# Sheet1_1.net
KiCad netlist of a schematic drawn in Altium Designer
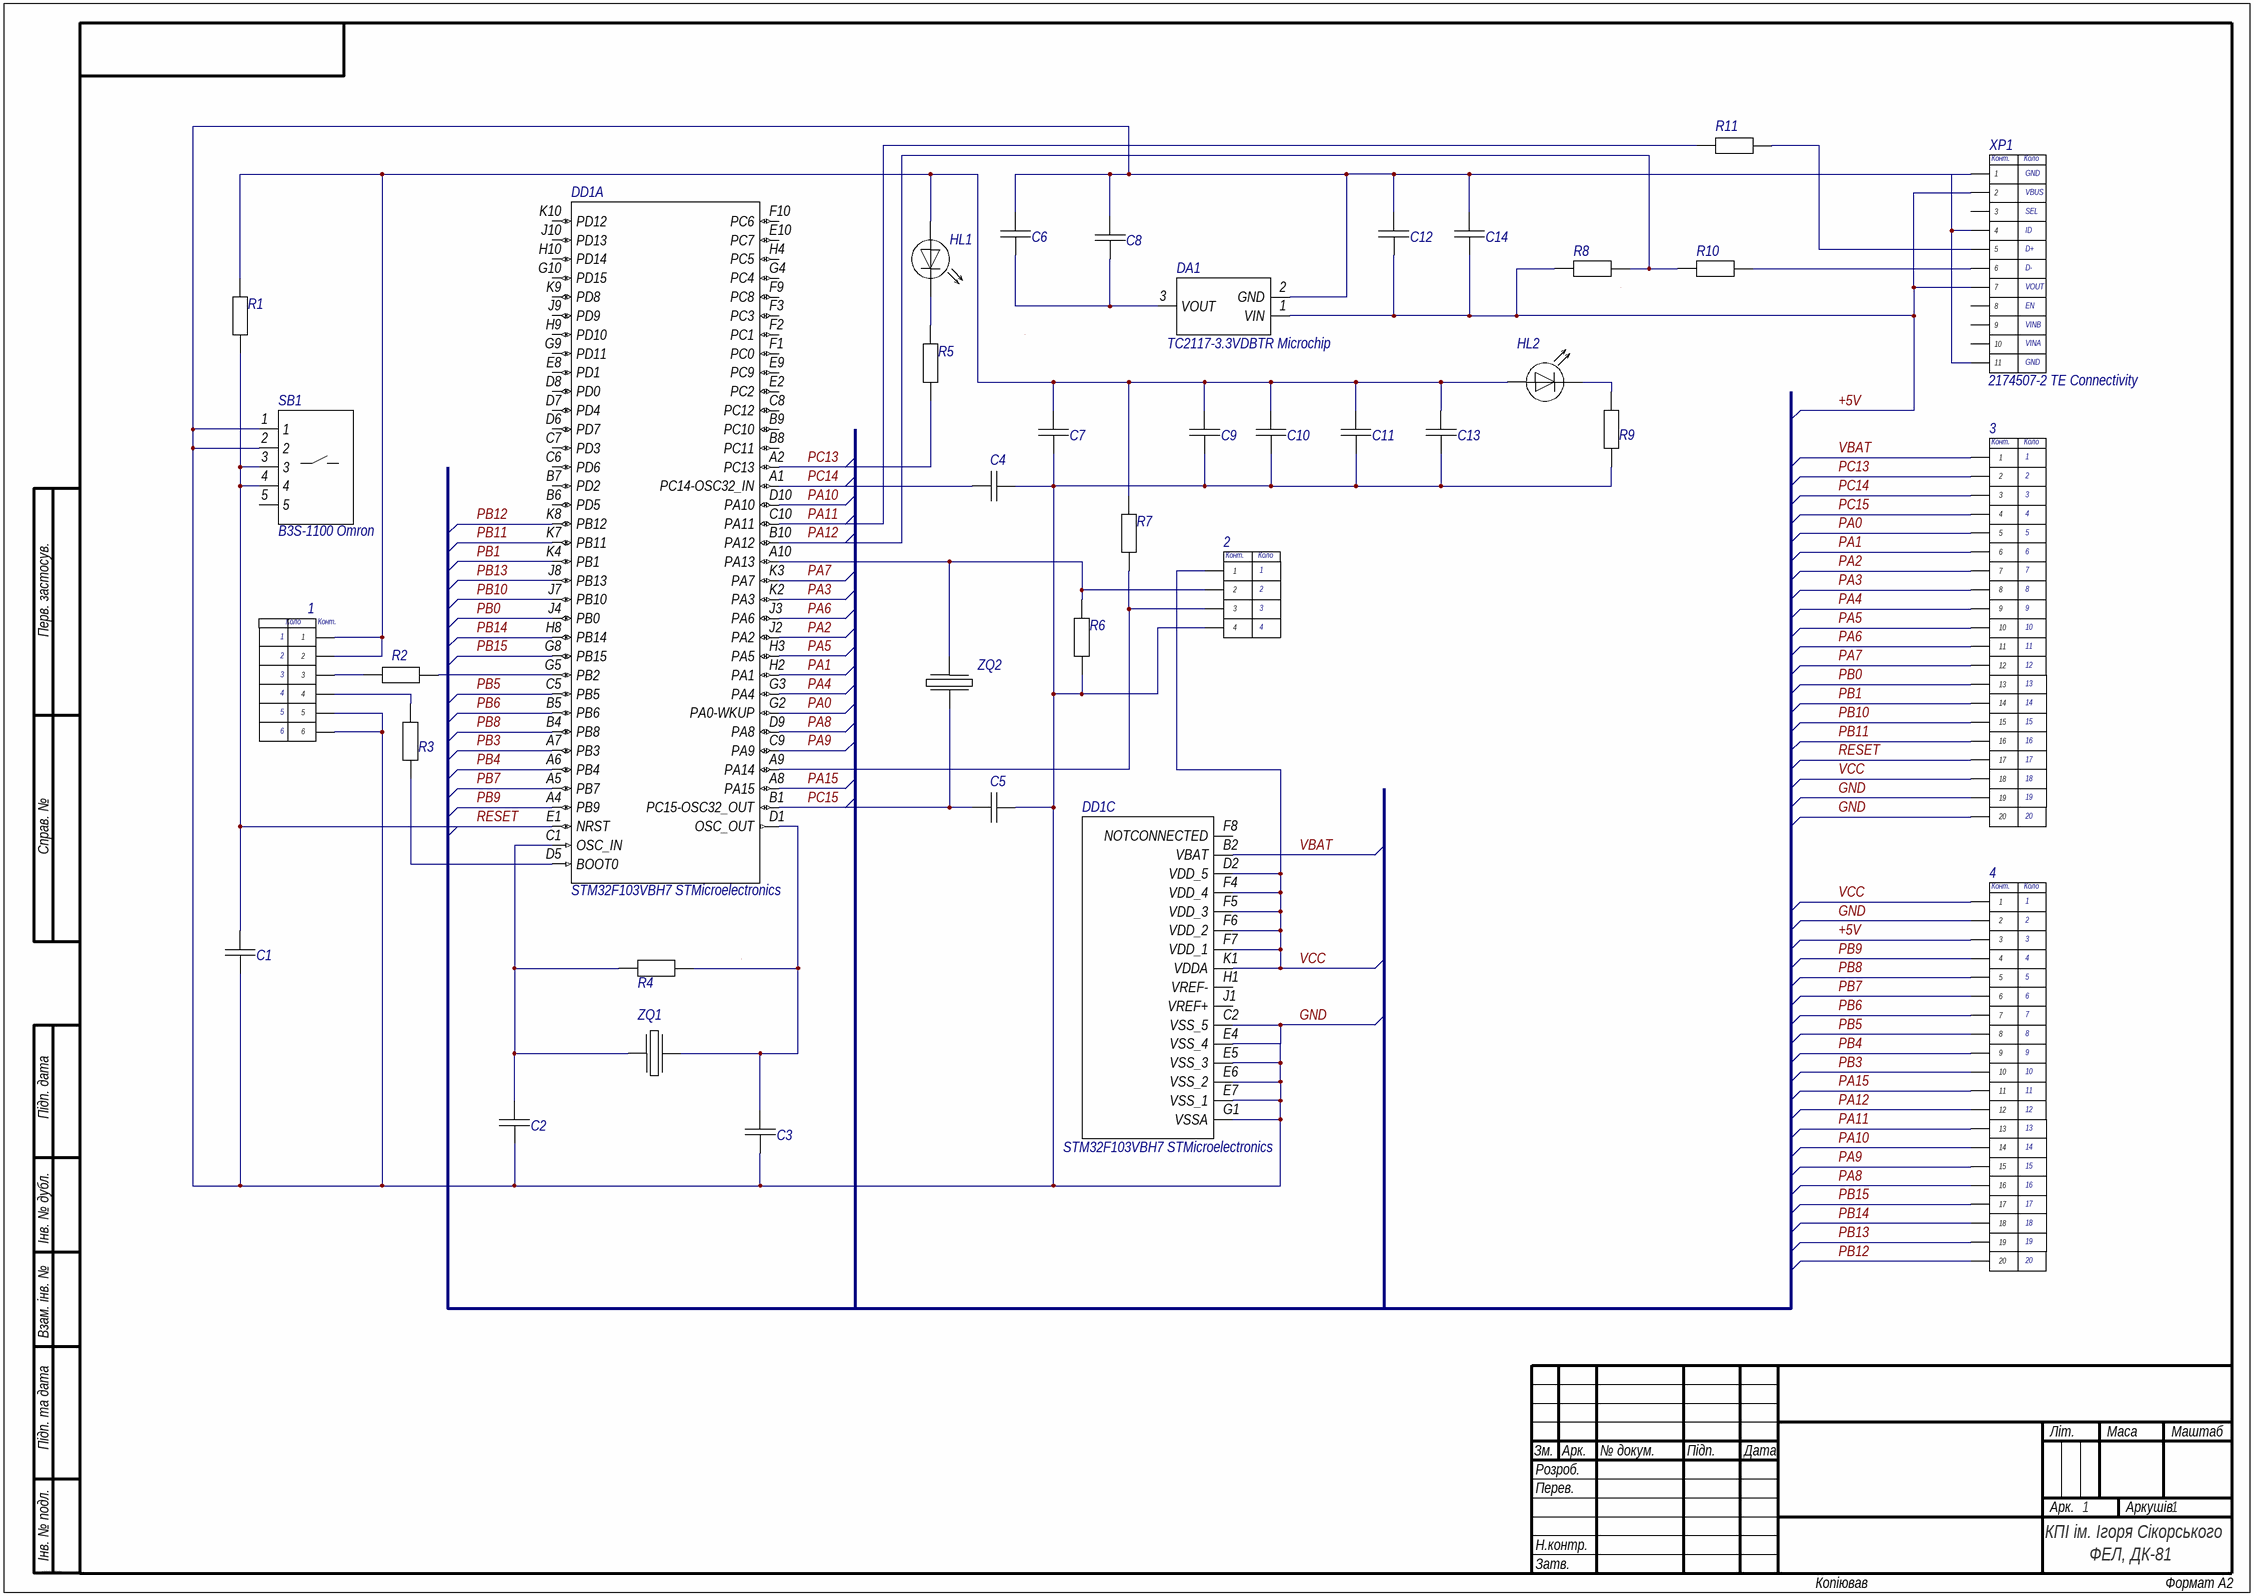
[diagram p0: Sheet1 (1).SchDoc]

(export (version "E")
  (design (tool "Eeschema 10.0.6"))
  (components
    (comp (ref "1")
      (value "pin_boot")
      (footprint "PIN_BOOT")
      (description "pads")
      (libsource (lib "Schlib1") (part "pin_boot"))
    )
    (comp (ref "2")
      (value "pins_jtag")
      (footprint "PIN_JTAG")
      (description "pads")
      (libsource (lib "Schlib1") (part "pins_jtag"))
    )
    (comp (ref "3")
      (value "pin_left")
      (footprint "pin_left")
      (description "pads")
      (libsource (lib "Schlib1") (part "pin_left"))
    )
    (comp (ref "4")
      (value "pin_right")
      (footprint "pin_right")
      (description "pads")
      (libsource (lib "Schlib1") (part "pin_right"))
    )
    (comp (ref "C1")
      (value "0603 63 В 1 мкФ 10% *")
      (footprint "C_0603")
      (fields (field (name "VOLTAGE") "63 В") (field (name "TOLERANCE") "10%"))
      (libsource (lib "Schlib1") (part "C 1 мкФ"))
    )
    (comp (ref "C2")
      (value "0603 63 В 20 пФ 10% *")
      (footprint "C_0603")
      (fields (field (name "VOLTAGE") "63 В") (field (name "TOLERANCE") "10%"))
      (libsource (lib "Schlib1") (part "C 20 пФ"))
    )
    (comp (ref "C3")
      (value "0603 63 В 20 пФ 10% *")
      (footprint "C_0603")
      (fields (field (name "VOLTAGE") "63 В") (field (name "TOLERANCE") "10%"))
      (libsource (lib "Schlib1") (part "C 20 пФ"))
    )
    (comp (ref "C4")
      (value "0603 63 В 20 пФ 10% *")
      (footprint "C_0603")
      (fields (field (name "VOLTAGE") "63 В") (field (name "TOLERANCE") "10%"))
      (libsource (lib "Schlib1") (part "C 20 пФ"))
    )
    (comp (ref "C5")
      (value "0603 63 В 20 пФ 10% *")
      (footprint "C_0603")
      (fields (field (name "VOLTAGE") "63 В") (field (name "TOLERANCE") "10%"))
      (libsource (lib "Schlib1") (part "C 20 пФ"))
    )
    (comp (ref "C6")
      (value "0603 63 В 100 нФ 10% *")
      (footprint "C_0603")
      (fields (field (name "VOLTAGE") "63 В") (field (name "TOLERANCE") "10%"))
      (libsource (lib "Schlib1") (part "C 100 нФ"))
    )
    (comp (ref "C7")
      (value "0603 63 В 100 нФ 10% *")
      (footprint "C_0603")
      (fields (field (name "VOLTAGE") "63 В") (field (name "TOLERANCE") "10%"))
      (libsource (lib "Schlib1") (part "C 100 нФ"))
    )
    (comp (ref "C8")
      (value "CASE-C_6032 63 В 330 мкФ 10% *")
      (footprint "CAPMP6.3X3.2_2.8N_KEM")
      (fields (field (name "VOLTAGE") "63 В") (field (name "TOLERANCE") "10%"))
      (libsource (lib "Schlib1") (part "C 330 мкФ"))
    )
    (comp (ref "C9")
      (value "0603 63 В 100 нФ 10% *")
      (footprint "C_0603")
      (fields (field (name "VOLTAGE") "63 В") (field (name "TOLERANCE") "10%"))
      (libsource (lib "Schlib1") (part "C 100 нФ"))
    )
    (comp (ref "C10")
      (value "0603 63 В 100 нФ 10% *")
      (footprint "C_0603")
      (fields (field (name "VOLTAGE") "63 В") (field (name "TOLERANCE") "10%"))
      (libsource (lib "Schlib1") (part "C 100 нФ"))
    )
    (comp (ref "C11")
      (value "0603 63 В 100 нФ 10% *")
      (footprint "C_0603")
      (fields (field (name "VOLTAGE") "63 В") (field (name "TOLERANCE") "10%"))
      (libsource (lib "Schlib1") (part "C 100 нФ"))
    )
    (comp (ref "C12")
      (value "CASE-C_6032 63 В 100 мкФ 10% *")
      (footprint "CAPMP6.3X3.2_2.8N_KEM")
      (fields (field (name "VOLTAGE") "63 В") (field (name "TOLERANCE") "10%"))
      (libsource (lib "Schlib1") (part "C 100 мкФ"))
    )
    (comp (ref "C13")
      (value "0603 63 В 100 нФ 10% *")
      (footprint "C_0603")
      (fields (field (name "VOLTAGE") "63 В") (field (name "TOLERANCE") "10%"))
      (libsource (lib "Schlib1") (part "C 100 нФ"))
    )
    (comp (ref "C14")
      (value "CASE-C_6032 63 В 100 мкФ 10% *")
      (footprint "CAPMP6.3X3.2_2.8N_KEM")
      (fields (field (name "VOLTAGE") "63 В") (field (name "TOLERANCE") "10%"))
      (libsource (lib "Schlib1") (part "C 100 мкФ"))
    )
    (comp (ref "DA1")
      (value "TC2117-3.3VDBTR Microchip")
      (footprint "TC2117")
      (fields (field (name "MANUFACTURER") "Microchip"))
      (libsource (lib "Schlib1") (part "TC2117-3.3VDBTR"))
    )
    (comp (ref "DD1")
      (value "STM32F103VBH7 STMicroelectronics")
      (footprint "LFBGA100")
      (fields (field (name "MANUFACTURER") "STMicroelectronics"))
      (libsource (lib "Schlib1") (part "STM32F103VBH7"))
    )
    (comp (ref "HL1")
      (value "XL-0603QYGC KENTO")
      (footprint "LED_DIALIGHT_598_DIA-M")
      (fields (field (name "MANUFACTURER") "KENTO"))
      (libsource (lib "Schlib1") (part "LED-0603"))
    )
    (comp (ref "HL2")
      (value "XL-0603QYGC KENTO")
      (footprint "LED_DIALIGHT_598_DIA-M")
      (fields (field (name "MANUFACTURER") "KENTO"))
      (libsource (lib "Schlib1") (part "LED-0603"))
    )
    (comp (ref "R1")
      (value "R-0603 0.1 Вт 10 кОм 10% Yageo")
      (footprint "R_0603")
      (fields
        (field (name "POWER") "0.1 Вт")
        (field (name "TOLERANCE") "10%")
        (field (name "MANUFACTURER") "Yageo")
      )
      (libsource (lib "Schlib1") (part "R 10 кОм"))
    )
    (comp (ref "R2")
      (value "R-0603 0.1 Вт 100 кОм 10% Yageo")
      (footprint "R_0603")
      (fields
        (field (name "POWER") "0.1 Вт")
        (field (name "TOLERANCE") "10%")
        (field (name "MANUFACTURER") "Yageo")
      )
      (libsource (lib "") (part "R 100 кОм_1"))
    )
    (comp (ref "R3")
      (value "R-0603 0.1 Вт 100 кОм 10% Yageo")
      (footprint "R_0603")
      (fields
        (field (name "POWER") "0.1 Вт")
        (field (name "TOLERANCE") "10%")
        (field (name "MANUFACTURER") "Yageo")
      )
      (libsource (lib "Schlib1") (part "R 100 кОм"))
    )
    (comp (ref "R4")
      (value "R-0603 0.1 Вт 1 МОм 10% Yageo")
      (footprint "R_0603")
      (fields
        (field (name "POWER") "0.1 Вт")
        (field (name "TOLERANCE") "10%")
        (field (name "MANUFACTURER") "Yageo")
      )
      (libsource (lib "Schlib1") (part "R 1 МОм"))
    )
    (comp (ref "R5")
      (value "R-0603 0.1 Вт 510 Ом 10% Yageo")
      (footprint "R_0603")
      (fields
        (field (name "POWER") "0.1 Вт")
        (field (name "TOLERANCE") "10%")
        (field (name "MANUFACTURER") "Yageo")
      )
      (libsource (lib "Schlib1") (part "R 510 Ом"))
    )
    (comp (ref "R6")
      (value "R-0603 0.1 Вт 10 кОм 10% Yageo")
      (footprint "R_0603")
      (fields
        (field (name "POWER") "0.1 Вт")
        (field (name "TOLERANCE") "10%")
        (field (name "MANUFACTURER") "Yageo")
      )
      (libsource (lib "Schlib1") (part "R 10 кОм"))
    )
    (comp (ref "R7")
      (value "R-0603 0.1 Вт 10 кОм 10% Yageo")
      (footprint "R_0603")
      (fields
        (field (name "POWER") "0.1 Вт")
        (field (name "TOLERANCE") "10%")
        (field (name "MANUFACTURER") "Yageo")
      )
      (libsource (lib "Schlib1") (part "R 10 кОм"))
    )
    (comp (ref "R8")
      (value "R-0603 0.1 Вт 1.5 кОм 10% Yageo")
      (footprint "R_0603")
      (fields
        (field (name "POWER") "0.1 Вт")
        (field (name "TOLERANCE") "10%")
        (field (name "MANUFACTURER") "Yageo")
      )
      (libsource (lib "Schlib1") (part "R 1.5 кОм"))
    )
    (comp (ref "R9")
      (value "R-0603 0.1 Вт 510 Ом 10% Yageo")
      (footprint "R_0603")
      (fields
        (field (name "POWER") "0.1 Вт")
        (field (name "TOLERANCE") "10%")
        (field (name "MANUFACTURER") "Yageo")
      )
      (libsource (lib "Schlib1") (part "R 510 Ом"))
    )
    (comp (ref "R10")
      (value "R-0603 0.1 Вт 20 Ом 10% Yageo")
      (footprint "R_0603")
      (fields
        (field (name "POWER") "0.1 Вт")
        (field (name "TOLERANCE") "10%")
        (field (name "MANUFACTURER") "Yageo")
      )
      (libsource (lib "Schlib1") (part "R 20 Ом"))
    )
    (comp (ref "R11")
      (value "R-0603 0.1 Вт 20 Ом 10% Yageo")
      (footprint "R_0603")
      (fields
        (field (name "POWER") "0.1 Вт")
        (field (name "TOLERANCE") "10%")
        (field (name "MANUFACTURER") "Yageo")
      )
      (libsource (lib "Schlib1") (part "R 20 Ом"))
    )
    (comp (ref "SB1")
      (value "B3S-1100 Omron")
      (footprint "SW_B3S-1100_OMR")
      (fields (field (name "MANUFACTURER") "Omron"))
      (libsource (lib "Schlib1") (part "B3S-1100"))
    )
    (comp (ref "XP1")
      (value "2174507-2 TE Connectivity")
      (footprint "CONN5_2013499-1_TEC - duplicate")
      (description "usb")
      (fields (field (name "MANUFACTURER") "TE Connectivity"))
      (libsource (lib "Schlib1") (part "2174507-2"))
    )
    (comp (ref "ZQ1")
      (value "OSC_8M LCSC")
      (footprint "HC-49S")
      (fields (field (name "MANUFACTURER") "LCSC"))
      (libsource (lib "Schlib1") (part "OSC_8M"))
    )
    (comp (ref "ZQ2")
      (value "OSC_32.7K LCSC")
      (footprint "SOJ_MC-306_EPS")
      (fields (field (name "MANUFACTURER") "LCSC"))
      (libsource (lib "Schlib1") (part "OSC_32.7K"))
    )
  )
  (nets
    (net (code "1") (name "/+5V") (class "Default")
      (node (ref "4") (pin "3") (pinfunction "3_3") (pintype "passive"))
      (node (ref "C12") (pin "1") (pinfunction "1_1") (pintype "passive"))
      (node (ref "C14") (pin "1") (pinfunction "1_1") (pintype "passive"))
      (node (ref "DA1") (pin "1") (pinfunction "VIN_1") (pintype "passive"))
      (node (ref "R8") (pin "1") (pinfunction "1_1") (pintype "passive"))
      (node (ref "XP1") (pin "2") (pinfunction "2_2") (pintype "passive"))
      (node (ref "XP1") (pin "7") (pinfunction "7_7") (pintype "passive"))
    )
    (net (code "2") (name "/GND") (class "Default")
      (node (ref "1") (pin "5") (pinfunction "5_5") (pintype "passive"))
      (node (ref "1") (pin "6") (pinfunction "6_6") (pintype "passive"))
      (node (ref "2") (pin "4") (pinfunction "4_4") (pintype "passive"))
      (node (ref "3") (pin "19") (pinfunction "19_19") (pintype "passive"))
      (node (ref "3") (pin "20") (pinfunction "20_20") (pintype "passive"))
      (node (ref "4") (pin "2") (pinfunction "2_2") (pintype "passive"))
      (node (ref "C1") (pin "1") (pinfunction "1_1") (pintype "passive"))
      (node (ref "C10") (pin "1") (pinfunction "1_1") (pintype "passive"))
      (node (ref "C11") (pin "1") (pinfunction "1_1") (pintype "passive"))
      (node (ref "C12") (pin "2") (pinfunction "2_2") (pintype "passive"))
      (node (ref "C13") (pin "1") (pinfunction "1_1") (pintype "passive"))
      (node (ref "C14") (pin "2") (pinfunction "2_2") (pintype "passive"))
      (node (ref "C2") (pin "1") (pinfunction "1_1") (pintype "passive"))
      (node (ref "C3") (pin "1") (pinfunction "1_1") (pintype "passive"))
      (node (ref "C4") (pin "2") (pinfunction "2_2") (pintype "passive"))
      (node (ref "C5") (pin "2") (pinfunction "2_2") (pintype "passive"))
      (node (ref "C6") (pin "2") (pinfunction "2_2") (pintype "passive"))
      (node (ref "C7") (pin "1") (pinfunction "1_1") (pintype "passive"))
      (node (ref "C8") (pin "2") (pinfunction "2_2") (pintype "passive"))
      (node (ref "C9") (pin "1") (pinfunction "1_1") (pintype "passive"))
      (node (ref "DA1") (pin "2") (pinfunction "GND_2") (pintype "passive"))
      (node (ref "DD1") (pin "C2") (pinfunction "VSS_5_C2") (pintype "power_in"))
      (node (ref "DD1") (pin "E4") (pinfunction "VSS_4_E4") (pintype "power_in"))
      (node (ref "DD1") (pin "E5") (pinfunction "VSS_3_E5") (pintype "power_in"))
      (node (ref "DD1") (pin "E6") (pinfunction "VSS_2_E6") (pintype "power_in"))
      (node (ref "DD1") (pin "E7") (pinfunction "VSS_1_E7") (pintype "power_in"))
      (node (ref "DD1") (pin "G1") (pinfunction "VSSA_G1") (pintype "power_in"))
      (node (ref "R6") (pin "1") (pinfunction "1_1") (pintype "passive"))
      (node (ref "R9") (pin "1") (pinfunction "1_1") (pintype "passive"))
      (node (ref "SB1") (pin "1") (pinfunction "1_1") (pintype "passive"))
      (node (ref "SB1") (pin "2") (pinfunction "2_2") (pintype "passive"))
      (node (ref "XP1") (pin "1") (pinfunction "1_1") (pintype "passive"))
      (node (ref "XP1") (pin "11") (pinfunction "11_11") (pintype "passive"))
      (node (ref "XP1") (pin "4") (pinfunction "4_4") (pintype "passive"))
    )
    (net (code "3") (name "/PA0") (class "Default")
      (node (ref "3") (pin "5") (pinfunction "5_5") (pintype "passive"))
      (node (ref "DD1") (pin "G2") (pinfunction "PA0-WKUP_G2") (pintype "bidirectional"))
    )
    (net (code "4") (name "/PA1") (class "Default")
      (node (ref "3") (pin "6") (pinfunction "6_6") (pintype "passive"))
      (node (ref "DD1") (pin "H2") (pinfunction "PA1_H2") (pintype "bidirectional"))
    )
    (net (code "5") (name "/PA2") (class "Default")
      (node (ref "3") (pin "7") (pinfunction "7_7") (pintype "passive"))
      (node (ref "DD1") (pin "J2") (pinfunction "PA2_J2") (pintype "bidirectional"))
    )
    (net (code "6") (name "/PA3") (class "Default")
      (node (ref "3") (pin "8") (pinfunction "8_8") (pintype "passive"))
      (node (ref "DD1") (pin "K2") (pinfunction "PA3_K2") (pintype "bidirectional"))
    )
    (net (code "7") (name "/PA4") (class "Default")
      (node (ref "3") (pin "9") (pinfunction "9_9") (pintype "passive"))
      (node (ref "DD1") (pin "G3") (pinfunction "PA4_G3") (pintype "bidirectional"))
    )
    (net (code "8") (name "/PA5") (class "Default")
      (node (ref "3") (pin "10") (pinfunction "10_10") (pintype "passive"))
      (node (ref "DD1") (pin "H3") (pinfunction "PA5_H3") (pintype "bidirectional"))
    )
    (net (code "9") (name "/PA6") (class "Default")
      (node (ref "3") (pin "11") (pinfunction "11_11") (pintype "passive"))
      (node (ref "DD1") (pin "J3") (pinfunction "PA6_J3") (pintype "bidirectional"))
    )
    (net (code "10") (name "/PA7") (class "Default")
      (node (ref "3") (pin "12") (pinfunction "12_12") (pintype "passive"))
      (node (ref "DD1") (pin "K3") (pinfunction "PA7_K3") (pintype "bidirectional"))
    )
    (net (code "11") (name "/PA8") (class "Default")
      (node (ref "4") (pin "16") (pinfunction "16_16") (pintype "passive"))
      (node (ref "DD1") (pin "D9") (pinfunction "PA8_D9") (pintype "bidirectional"))
    )
    (net (code "12") (name "/PA9") (class "Default")
      (node (ref "4") (pin "15") (pinfunction "15_15") (pintype "passive"))
      (node (ref "DD1") (pin "C9") (pinfunction "PA9_C9") (pintype "bidirectional"))
    )
    (net (code "13") (name "/PA10") (class "Default")
      (node (ref "4") (pin "14") (pinfunction "14_14") (pintype "passive"))
      (node (ref "DD1") (pin "D10") (pinfunction "PA10_D10") (pintype "bidirectional"))
    )
    (net (code "14") (name "/PA11") (class "Default")
      (node (ref "4") (pin "13") (pinfunction "13_13") (pintype "passive"))
      (node (ref "DD1") (pin "C10") (pinfunction "PA11_C10") (pintype "bidirectional"))
      (node (ref "R11") (pin "1") (pinfunction "1_1") (pintype "passive"))
    )
    (net (code "15") (name "/PA12") (class "Default")
      (node (ref "4") (pin "12") (pinfunction "12_12") (pintype "passive"))
      (node (ref "DD1") (pin "B10") (pinfunction "PA12_B10") (pintype "bidirectional"))
      (node (ref "R10") (pin "1") (pinfunction "1_1") (pintype "passive"))
      (node (ref "R8") (pin "2") (pinfunction "2_2") (pintype "passive"))
    )
    (net (code "16") (name "/PA15") (class "Default")
      (node (ref "4") (pin "11") (pinfunction "11_11") (pintype "passive"))
      (node (ref "DD1") (pin "A8") (pinfunction "PA15_A8") (pintype "bidirectional"))
    )
    (net (code "17") (name "/PB0") (class "Default")
      (node (ref "3") (pin "13") (pinfunction "13_13") (pintype "passive"))
      (node (ref "DD1") (pin "J4") (pinfunction "PB0_J4") (pintype "bidirectional"))
    )
    (net (code "18") (name "/PB1") (class "Default")
      (node (ref "3") (pin "14") (pinfunction "14_14") (pintype "passive"))
      (node (ref "DD1") (pin "K4") (pinfunction "PB1_K4") (pintype "bidirectional"))
    )
    (net (code "19") (name "/PB3") (class "Default")
      (node (ref "4") (pin "10") (pinfunction "10_10") (pintype "passive"))
      (node (ref "DD1") (pin "A7") (pinfunction "PB3_A7") (pintype "bidirectional"))
    )
    (net (code "20") (name "/PB4") (class "Default")
      (node (ref "4") (pin "9") (pinfunction "9_9") (pintype "passive"))
      (node (ref "DD1") (pin "A6") (pinfunction "PB4_A6") (pintype "bidirectional"))
    )
    (net (code "21") (name "/PB5") (class "Default")
      (node (ref "4") (pin "8") (pinfunction "8_8") (pintype "passive"))
      (node (ref "DD1") (pin "C5") (pinfunction "PB5_C5") (pintype "bidirectional"))
    )
    (net (code "22") (name "/PB6") (class "Default")
      (node (ref "4") (pin "7") (pinfunction "7_7") (pintype "passive"))
      (node (ref "DD1") (pin "B5") (pinfunction "PB6_B5") (pintype "bidirectional"))
    )
    (net (code "23") (name "/PB7") (class "Default")
      (node (ref "4") (pin "6") (pinfunction "6_6") (pintype "passive"))
      (node (ref "DD1") (pin "A5") (pinfunction "PB7_A5") (pintype "bidirectional"))
    )
    (net (code "24") (name "/PB8") (class "Default")
      (node (ref "4") (pin "5") (pinfunction "5_5") (pintype "passive"))
      (node (ref "DD1") (pin "B4") (pinfunction "PB8_B4") (pintype "bidirectional"))
    )
    (net (code "25") (name "/PB9") (class "Default")
      (node (ref "4") (pin "4") (pinfunction "4_4") (pintype "passive"))
      (node (ref "DD1") (pin "A4") (pinfunction "PB9_A4") (pintype "bidirectional"))
    )
    (net (code "26") (name "/PB10") (class "Default")
      (node (ref "3") (pin "15") (pinfunction "15_15") (pintype "passive"))
      (node (ref "DD1") (pin "J7") (pinfunction "PB10_J7") (pintype "bidirectional"))
    )
    (net (code "27") (name "/PB11") (class "Default")
      (node (ref "3") (pin "16") (pinfunction "16_16") (pintype "passive"))
      (node (ref "DD1") (pin "K7") (pinfunction "PB11_K7") (pintype "bidirectional"))
    )
    (net (code "28") (name "/PB12") (class "Default")
      (node (ref "4") (pin "20") (pinfunction "20_20") (pintype "passive"))
      (node (ref "DD1") (pin "K8") (pinfunction "PB12_K8") (pintype "bidirectional"))
    )
    (net (code "29") (name "/PB13") (class "Default")
      (node (ref "4") (pin "19") (pinfunction "19_19") (pintype "passive"))
      (node (ref "DD1") (pin "J8") (pinfunction "PB13_J8") (pintype "bidirectional"))
    )
    (net (code "30") (name "/PB14") (class "Default")
      (node (ref "4") (pin "18") (pinfunction "18_18") (pintype "passive"))
      (node (ref "DD1") (pin "H8") (pinfunction "PB14_H8") (pintype "bidirectional"))
    )
    (net (code "31") (name "/PB15") (class "Default")
      (node (ref "4") (pin "17") (pinfunction "17_17") (pintype "passive"))
      (node (ref "DD1") (pin "G8") (pinfunction "PB15_G8") (pintype "bidirectional"))
    )
    (net (code "32") (name "/PC13") (class "Default")
      (node (ref "3") (pin "2") (pinfunction "2_2") (pintype "passive"))
      (node (ref "DD1") (pin "A2") (pinfunction "PC13_A2") (pintype "bidirectional"))
      (node (ref "R5") (pin "1") (pinfunction "1_1") (pintype "passive"))
    )
    (net (code "33") (name "/PC14") (class "Default")
      (node (ref "3") (pin "3") (pinfunction "3_3") (pintype "passive"))
      (node (ref "C4") (pin "1") (pinfunction "1_1") (pintype "passive"))
      (node (ref "DD1") (pin "A1") (pinfunction "PC14-OSC32_IN_A1") (pintype "bidirectional"))
    )
    (net (code "34") (name "/PC15") (class "Default")
      (node (ref "3") (pin "4") (pinfunction "4_4") (pintype "passive"))
      (node (ref "C5") (pin "1") (pinfunction "1_1") (pintype "passive"))
      (node (ref "DD1") (pin "B1") (pinfunction "PC15-OSC32_OUT_B1") (pintype "bidirectional"))
      (node (ref "ZQ2") (pin "2") (pinfunction "2_2") (pintype "passive"))
    )
    (net (code "35") (name "/RESET") (class "Default")
      (node (ref "3") (pin "17") (pinfunction "17_17") (pintype "passive"))
      (node (ref "C1") (pin "2") (pinfunction "2_2") (pintype "passive"))
      (node (ref "DD1") (pin "E1") (pinfunction "NRST_E1") (pintype "bidirectional"))
      (node (ref "R1") (pin "1") (pinfunction "1_1") (pintype "passive"))
      (node (ref "SB1") (pin "3") (pinfunction "3_3") (pintype "passive"))
      (node (ref "SB1") (pin "4") (pinfunction "4_4") (pintype "passive"))
    )
    (net (code "36") (name "/VBAT") (class "Default")
      (node (ref "3") (pin "1") (pinfunction "1_1") (pintype "passive"))
      (node (ref "DD1") (pin "B2") (pinfunction "VBAT_B2") (pintype "power_in"))
    )
    (net (code "37") (name "/VCC") (class "Default")
      (node (ref "2") (pin "1") (pinfunction "1_1") (pintype "passive"))
      (node (ref "3") (pin "18") (pinfunction "18_18") (pintype "passive"))
      (node (ref "4") (pin "1") (pinfunction "1_1") (pintype "passive"))
      (node (ref "DD1") (pin "D2") (pinfunction "VDD_5_D2") (pintype "power_in"))
      (node (ref "DD1") (pin "F4") (pinfunction "VDD_4_F4") (pintype "power_in"))
      (node (ref "DD1") (pin "F5") (pinfunction "VDD_3_F5") (pintype "power_in"))
      (node (ref "DD1") (pin "F6") (pinfunction "VDD_2_F6") (pintype "power_in"))
      (node (ref "DD1") (pin "F7") (pinfunction "VDD_1_F7") (pintype "power_in"))
      (node (ref "DD1") (pin "K1") (pinfunction "VDDA_K1") (pintype "power_in"))
    )
    (net (code "38") (name "Net-(1-Pad1)") (class "Default")
      (node (ref "1") (pin "1") (pinfunction "1_1") (pintype "passive"))
      (node (ref "1") (pin "2") (pinfunction "2_2") (pintype "passive"))
      (node (ref "C10") (pin "2") (pinfunction "2_2") (pintype "passive"))
      (node (ref "C11") (pin "2") (pinfunction "2_2") (pintype "passive"))
      (node (ref "C13") (pin "2") (pinfunction "2_2") (pintype "passive"))
      (node (ref "C7") (pin "2") (pinfunction "2_2") (pintype "passive"))
      (node (ref "C9") (pin "2") (pinfunction "2_2") (pintype "passive"))
      (node (ref "HL1") (pin "1") (pinfunction "1_1") (pintype "passive"))
      (node (ref "HL2") (pin "1") (pinfunction "1_1") (pintype "passive"))
      (node (ref "R1") (pin "2") (pinfunction "2_2") (pintype "passive"))
      (node (ref "R7") (pin "2") (pinfunction "2_2") (pintype "passive"))
    )
    (net (code "39") (name "Net-(1-Pad3)") (class "Default")
      (node (ref "1") (pin "3") (pinfunction "3_3") (pintype "passive"))
      (node (ref "R2") (pin "1") (pinfunction "1_1") (pintype "passive"))
    )
    (net (code "40") (name "Net-(1-Pad4)") (class "Default")
      (node (ref "1") (pin "4") (pinfunction "4_4") (pintype "passive"))
      (node (ref "R3") (pin "2") (pinfunction "2_2") (pintype "passive"))
    )
    (net (code "41") (name "Net-(DA1-VOUT)") (class "Default")
      (node (ref "C6") (pin "1") (pinfunction "1_1") (pintype "passive"))
      (node (ref "C8") (pin "1") (pinfunction "1_1") (pintype "passive"))
      (node (ref "DA1") (pin "3") (pinfunction "VOUT_3") (pintype "passive"))
    )
    (net (code "42") (name "Net-(DD1A-BOOT0)") (class "Default")
      (node (ref "DD1") (pin "D5") (pinfunction "BOOT0_D5") (pintype "input"))
      (node (ref "R3") (pin "1") (pinfunction "1_1") (pintype "passive"))
    )
    (net (code "43") (name "Net-(DD1A-OSC_IN)") (class "Default")
      (node (ref "C2") (pin "2") (pinfunction "2_2") (pintype "passive"))
      (node (ref "DD1") (pin "C1") (pinfunction "OSC_IN_C1") (pintype "input"))
      (node (ref "R4") (pin "2") (pinfunction "2_2") (pintype "passive"))
      (node (ref "ZQ1") (pin "1") (pinfunction "1_1") (pintype "passive"))
    )
    (net (code "44") (name "Net-(DD1A-OSC_OUT)") (class "Default")
      (node (ref "C3") (pin "2") (pinfunction "2_2") (pintype "passive"))
      (node (ref "DD1") (pin "D1") (pinfunction "OSC_OUT_D1") (pintype "output"))
      (node (ref "R4") (pin "1") (pinfunction "1_1") (pintype "passive"))
      (node (ref "ZQ1") (pin "2") (pinfunction "2_2") (pintype "passive"))
    )
    (net (code "45") (name "Net-(DD1A-PA13)") (class "Default")
      (node (ref "2") (pin "2") (pinfunction "2_2") (pintype "passive"))
      (node (ref "DD1") (pin "A10") (pinfunction "PA13_A10") (pintype "bidirectional"))
      (node (ref "R6") (pin "2") (pinfunction "2_2") (pintype "passive"))
      (node (ref "ZQ2") (pin "1") (pinfunction "1_1") (pintype "passive"))
    )
    (net (code "46") (name "Net-(DD1A-PA14)") (class "Default")
      (node (ref "2") (pin "3") (pinfunction "3_3") (pintype "passive"))
      (node (ref "DD1") (pin "A9") (pinfunction "PA14_A9") (pintype "bidirectional"))
      (node (ref "R7") (pin "1") (pinfunction "1_1") (pintype "passive"))
    )
    (net (code "47") (name "Net-(DD1A-PB2)") (class "Default")
      (node (ref "DD1") (pin "G5") (pinfunction "PB2_G5") (pintype "bidirectional"))
      (node (ref "R2") (pin "2") (pinfunction "2_2") (pintype "passive"))
    )
    (net (code "48") (name "Net-(HL1-Pad2)") (class "Default")
      (node (ref "HL1") (pin "2") (pinfunction "2_2") (pintype "passive"))
      (node (ref "R5") (pin "2") (pinfunction "2_2") (pintype "passive"))
    )
    (net (code "49") (name "Net-(HL2-Pad2)") (class "Default")
      (node (ref "HL2") (pin "2") (pinfunction "2_2") (pintype "passive"))
      (node (ref "R9") (pin "2") (pinfunction "2_2") (pintype "passive"))
    )
    (net (code "50") (name "Net-(R10-Pad2)") (class "Default")
      (node (ref "R10") (pin "2") (pinfunction "2_2") (pintype "passive"))
      (node (ref "XP1") (pin "6") (pinfunction "6_6") (pintype "passive"))
    )
    (net (code "51") (name "Net-(R11-Pad2)") (class "Default")
      (node (ref "R11") (pin "2") (pinfunction "2_2") (pintype "passive"))
      (node (ref "XP1") (pin "5") (pinfunction "5_5") (pintype "passive"))
    )
    (net (code "52") (name "unconnected-(DD1A-PC0-PadF1)") (class "Default")
      (node (ref "DD1") (pin "F1") (pinfunction "PC0_F1") (pintype "bidirectional"))
    )
    (net (code "53") (name "unconnected-(DD1A-PC1-PadF2)") (class "Default")
      (node (ref "DD1") (pin "F2") (pinfunction "PC1_F2") (pintype "bidirectional"))
    )
    (net (code "54") (name "unconnected-(DD1A-PC2-PadE2)") (class "Default")
      (node (ref "DD1") (pin "E2") (pinfunction "PC2_E2") (pintype "bidirectional"))
    )
    (net (code "55") (name "unconnected-(DD1A-PC3-PadF3)") (class "Default")
      (node (ref "DD1") (pin "F3") (pinfunction "PC3_F3") (pintype "bidirectional"))
    )
    (net (code "56") (name "unconnected-(DD1A-PC4-PadG4)") (class "Default")
      (node (ref "DD1") (pin "G4") (pinfunction "PC4_G4") (pintype "bidirectional"))
    )
    (net (code "57") (name "unconnected-(DD1A-PC5-PadH4)") (class "Default")
      (node (ref "DD1") (pin "H4") (pinfunction "PC5_H4") (pintype "bidirectional"))
    )
    (net (code "58") (name "unconnected-(DD1A-PC6-PadF10)") (class "Default")
      (node (ref "DD1") (pin "F10") (pinfunction "PC6_F10") (pintype "bidirectional"))
    )
    (net (code "59") (name "unconnected-(DD1A-PC7-PadE10)") (class "Default")
      (node (ref "DD1") (pin "E10") (pinfunction "PC7_E10") (pintype "bidirectional"))
    )
    (net (code "60") (name "unconnected-(DD1A-PC8-PadF9)") (class "Default")
      (node (ref "DD1") (pin "F9") (pinfunction "PC8_F9") (pintype "bidirectional"))
    )
    (net (code "61") (name "unconnected-(DD1A-PC9-PadE9)") (class "Default")
      (node (ref "DD1") (pin "E9") (pinfunction "PC9_E9") (pintype "bidirectional"))
    )
    (net (code "62") (name "unconnected-(DD1A-PC10-PadB9)") (class "Default")
      (node (ref "DD1") (pin "B9") (pinfunction "PC10_B9") (pintype "bidirectional"))
    )
    (net (code "63") (name "unconnected-(DD1A-PC11-PadB8)") (class "Default")
      (node (ref "DD1") (pin "B8") (pinfunction "PC11_B8") (pintype "bidirectional"))
    )
    (net (code "64") (name "unconnected-(DD1A-PC12-PadC8)") (class "Default")
      (node (ref "DD1") (pin "C8") (pinfunction "PC12_C8") (pintype "bidirectional"))
    )
    (net (code "65") (name "unconnected-(DD1A-PD0-PadD8)") (class "Default")
      (node (ref "DD1") (pin "D8") (pinfunction "PD0_D8") (pintype "bidirectional"))
    )
    (net (code "66") (name "unconnected-(DD1A-PD1-PadE8)") (class "Default")
      (node (ref "DD1") (pin "E8") (pinfunction "PD1_E8") (pintype "bidirectional"))
    )
    (net (code "67") (name "unconnected-(DD1A-PD2-PadB7)") (class "Default")
      (node (ref "DD1") (pin "B7") (pinfunction "PD2_B7") (pintype "bidirectional"))
    )
    (net (code "68") (name "unconnected-(DD1A-PD3-PadC7)") (class "Default")
      (node (ref "DD1") (pin "C7") (pinfunction "PD3_C7") (pintype "bidirectional"))
    )
    (net (code "69") (name "unconnected-(DD1A-PD4-PadD7)") (class "Default")
      (node (ref "DD1") (pin "D7") (pinfunction "PD4_D7") (pintype "bidirectional"))
    )
    (net (code "70") (name "unconnected-(DD1A-PD5-PadB6)") (class "Default")
      (node (ref "DD1") (pin "B6") (pinfunction "PD5_B6") (pintype "bidirectional"))
    )
    (net (code "71") (name "unconnected-(DD1A-PD6-PadC6)") (class "Default")
      (node (ref "DD1") (pin "C6") (pinfunction "PD6_C6") (pintype "bidirectional"))
    )
    (net (code "72") (name "unconnected-(DD1A-PD7-PadD6)") (class "Default")
      (node (ref "DD1") (pin "D6") (pinfunction "PD7_D6") (pintype "bidirectional"))
    )
    (net (code "73") (name "unconnected-(DD1A-PD8-PadK9)") (class "Default")
      (node (ref "DD1") (pin "K9") (pinfunction "PD8_K9") (pintype "bidirectional"))
    )
    (net (code "74") (name "unconnected-(DD1A-PD9-PadJ9)") (class "Default")
      (node (ref "DD1") (pin "J9") (pinfunction "PD9_J9") (pintype "bidirectional"))
    )
    (net (code "75") (name "unconnected-(DD1A-PD10-PadH9)") (class "Default")
      (node (ref "DD1") (pin "H9") (pinfunction "PD10_H9") (pintype "bidirectional"))
    )
    (net (code "76") (name "unconnected-(DD1A-PD11-PadG9)") (class "Default")
      (node (ref "DD1") (pin "G9") (pinfunction "PD11_G9") (pintype "bidirectional"))
    )
    (net (code "77") (name "unconnected-(DD1A-PD12-PadK10)") (class "Default")
      (node (ref "DD1") (pin "K10") (pinfunction "PD12_K10") (pintype "bidirectional"))
    )
    (net (code "78") (name "unconnected-(DD1A-PD13-PadJ10)") (class "Default")
      (node (ref "DD1") (pin "J10") (pinfunction "PD13_J10") (pintype "bidirectional"))
    )
    (net (code "79") (name "unconnected-(DD1A-PD14-PadH10)") (class "Default")
      (node (ref "DD1") (pin "H10") (pinfunction "PD14_H10") (pintype "bidirectional"))
    )
    (net (code "80") (name "unconnected-(DD1A-PD15-PadG10)") (class "Default")
      (node (ref "DD1") (pin "G10") (pinfunction "PD15_G10") (pintype "bidirectional"))
    )
    (net (code "81") (name "unconnected-(DD1C-NOTCONNECTED-PadF8)") (class "Default")
      (node (ref "DD1") (pin "F8") (pinfunction "NOTCONNECTED_F8") (pintype "passive"))
    )
    (net (code "82") (name "unconnected-(DD1C-VREF+-PadJ1)") (class "Default")
      (node (ref "DD1") (pin "J1") (pinfunction "VREF+_J1") (pintype "power_in"))
    )
    (net (code "83") (name "unconnected-(DD1C-VREF--PadH1)") (class "Default")
      (node (ref "DD1") (pin "H1") (pinfunction "VREF-_H1") (pintype "power_in"))
    )
    (net (code "84") (name "unconnected-(SB1-Pad5)") (class "Default")
      (node (ref "SB1") (pin "5") (pinfunction "5_5") (pintype "passive"))
    )
    (net (code "85") (name "unconnected-(XP1-Pad3)") (class "Default")
      (node (ref "XP1") (pin "3") (pinfunction "3_3") (pintype "passive"))
    )
    (net (code "86") (name "unconnected-(XP1-Pad8)") (class "Default")
      (node (ref "XP1") (pin "8") (pinfunction "8_8") (pintype "passive"))
    )
    (net (code "87") (name "unconnected-(XP1-Pad9)") (class "Default")
      (node (ref "XP1") (pin "9") (pinfunction "9_9") (pintype "passive"))
    )
    (net (code "88") (name "unconnected-(XP1-Pad10)") (class "Default")
      (node (ref "XP1") (pin "10") (pinfunction "10_10") (pintype "passive"))
    )
  )
)
